# 1ms_Debouncer.net
KiCad netlist of a schematic drawn in Altium Designer
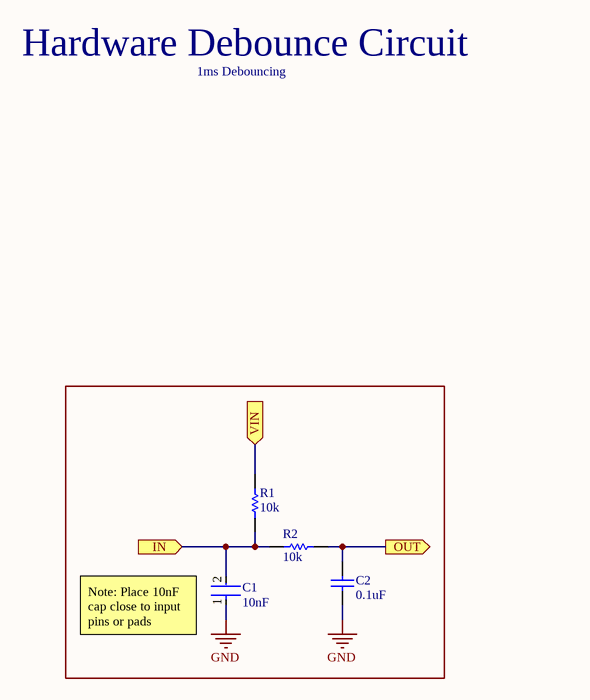
[diagram p0: 1ms Debouncer.SchDoc]

(export (version "E")
  (design (tool "Eeschema 10.0.6"))
  (components
    (comp (ref "C1")
      (value "10nF")
      (footprint "FP-CL21-IPC_A")
      (description "CL21 Series 0805 10nF 100V ±10% Tolerance X7R Multilayer Ceramic Chip Capacitor")
      (fields (field (name "VOLTAGE") "100V") (field (name "TOLERANCE") "10%"))
      (libsource (lib "Altium Content Vault") (part "b4654b650e69147ec39a6b967a45e02"))
    )
    (comp (ref "C2")
      (value "0.1uF")
      (footprint "CAPC2013X95X45ML10T25")
      (description "Chip Capacitor, 0.1 uF, +/- 10%, 50 V, 0805 (2012 Metric), RoHS, Tape and Reel")
      (fields
        (field (name "MANUFACTURER") "Samsung Electro-Mechanics")
        (field (name "MANUFACTURER PART NUMBER") "CL21B104KBCNNNC")
      )
      (libsource (lib "Altium Content Vault") (part "CAP-NP-2"))
    )
    (comp (ref "R1")
      (value "10k")
      (footprint "RESC2013X70X40LL20T20")
      (fields
        (field (name "PART NUMBER") "ERJ-6GEYJ103V")
        (field (name "MANUFACTURER") "Panasonic")
        (field (name "TOLERANCE") "5%")
      )
      (libsource (lib "Altium Content Vault") (part "RES"))
    )
    (comp (ref "R2")
      (value "10k")
      (footprint "RESC2013X70X40LL20T20")
      (fields
        (field (name "PART NUMBER") "ERJ-6GEYJ103V")
        (field (name "MANUFACTURER") "Panasonic")
        (field (name "TOLERANCE") "5%")
      )
      (libsource (lib "Altium Content Vault") (part "RES"))
    )
  )
  (nets
    (net (code "1") (name "/IN") (class "Default")
      (node (ref "C1") (pin "2") (pinfunction "2_2") (pintype "passive"))
      (node (ref "R1") (pin "1") (pinfunction "1_1") (pintype "passive"))
      (node (ref "R2") (pin "2") (pinfunction "2_2") (pintype "passive"))
    )
    (net (code "2") (name "/OUT") (class "Default")
      (node (ref "C2") (pin "1") (pinfunction "1_1") (pintype "passive"))
      (node (ref "R2") (pin "1") (pinfunction "1_1") (pintype "passive"))
    )
    (net (code "3") (name "/VIN") (class "Default")
      (node (ref "R1") (pin "2") (pinfunction "2_2") (pintype "passive"))
    )
    (net (code "4") (name "GND") (class "Default")
      (node (ref "C1") (pin "1") (pinfunction "1_1") (pintype "passive"))
      (node (ref "C2") (pin "2") (pinfunction "2_2") (pintype "passive"))
    )
  )
)
